# 8k-nolink.net
KiCad netlist of a schematic drawn in EAGLE
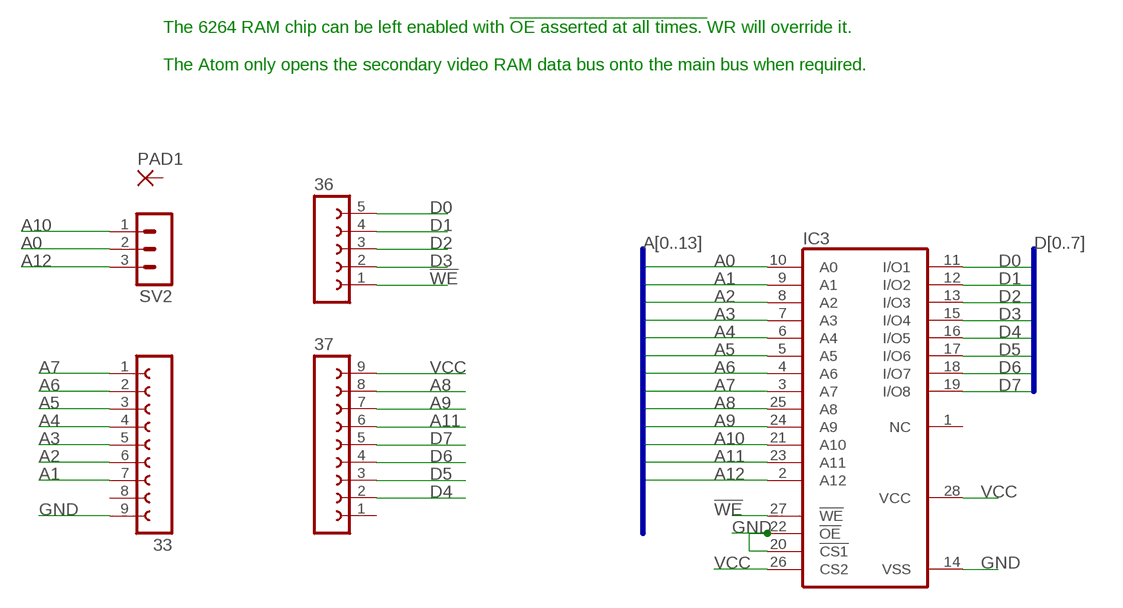
[diagram p0: schematic, sheet 1]

(export (version "E")
  (design (tool "Eeschema 10.0.6"))
  (components
    (comp (ref "33")
      (value "FE09-1")
      (footprint "eagle-import:FE09")
      (libsource (lib "eagle-import") (part "FE09-1"))
    )
    (comp (ref "36")
      (value "FE05-1")
      (footprint "eagle-import:FE05-1")
      (libsource (lib "eagle-import") (part "FE05-1"))
    )
    (comp (ref "37")
      (value "FE09-1")
      (footprint "eagle-import:FE09")
      (libsource (lib "eagle-import") (part "FE09-1"))
    )
    (comp (ref "IC3")
      (value "6264A")
      (footprint "eagle-import:DIL28-6")
      (libsource (lib "eagle-import") (part "6264A"))
    )
    (comp (ref "PAD1")
      (value "1,6/0,8")
      (footprint "eagle-import:1,6_0,8")
      (libsource (lib "eagle-import") (part "1,6/0,8"))
    )
    (comp (ref "SV2")
      (value "MA03-1")
      (footprint "eagle-import:MA03-1")
      (libsource (lib "eagle-import") (part "MA03-1"))
    )
  )
  (nets
    (net (code "2") (name "/A0") (class "Default")
      (node (ref "IC3") (pin "10") (pinfunction "A0_10") (pintype "input"))
      (node (ref "SV2") (pin "2") (pinfunction "2_2") (pintype "passive"))
    )
    (net (code "3") (name "/A1") (class "Default")
      (node (ref "33") (pin "7") (pinfunction "7_7") (pintype "passive"))
      (node (ref "IC3") (pin "9") (pinfunction "A1_9") (pintype "input"))
    )
    (net (code "4") (name "/A2") (class "Default")
      (node (ref "33") (pin "6") (pinfunction "6_6") (pintype "passive"))
      (node (ref "IC3") (pin "8") (pinfunction "A2_8") (pintype "input"))
    )
    (net (code "5") (name "/A3") (class "Default")
      (node (ref "33") (pin "5") (pinfunction "5_5") (pintype "passive"))
      (node (ref "IC3") (pin "7") (pinfunction "A3_7") (pintype "input"))
    )
    (net (code "6") (name "/A4") (class "Default")
      (node (ref "33") (pin "4") (pinfunction "4_4") (pintype "passive"))
      (node (ref "IC3") (pin "6") (pinfunction "A4_6") (pintype "input"))
    )
    (net (code "7") (name "/A5") (class "Default")
      (node (ref "33") (pin "3") (pinfunction "3_3") (pintype "passive"))
      (node (ref "IC3") (pin "5") (pinfunction "A5_5") (pintype "input"))
    )
    (net (code "8") (name "/A6") (class "Default")
      (node (ref "33") (pin "2") (pinfunction "2_2") (pintype "passive"))
      (node (ref "IC3") (pin "4") (pinfunction "A6_4") (pintype "input"))
    )
    (net (code "9") (name "/A7") (class "Default")
      (node (ref "33") (pin "1") (pinfunction "1_1") (pintype "passive"))
      (node (ref "IC3") (pin "3") (pinfunction "A7_3") (pintype "input"))
    )
    (net (code "10") (name "/A8") (class "Default")
      (node (ref "37") (pin "8") (pinfunction "8_8") (pintype "passive"))
      (node (ref "IC3") (pin "25") (pinfunction "A8_25") (pintype "input"))
    )
    (net (code "11") (name "/A9") (class "Default")
      (node (ref "37") (pin "7") (pinfunction "7_7") (pintype "passive"))
      (node (ref "IC3") (pin "24") (pinfunction "A9_24") (pintype "input"))
    )
    (net (code "12") (name "/A10") (class "Default")
      (node (ref "IC3") (pin "21") (pinfunction "A10_21") (pintype "input"))
      (node (ref "SV2") (pin "1") (pinfunction "1_1") (pintype "passive"))
    )
    (net (code "13") (name "/A11") (class "Default")
      (node (ref "37") (pin "6") (pinfunction "6_6") (pintype "passive"))
      (node (ref "IC3") (pin "23") (pinfunction "A11_23") (pintype "input"))
    )
    (net (code "14") (name "/A12") (class "Default")
      (node (ref "IC3") (pin "2") (pinfunction "A12_2") (pintype "input"))
      (node (ref "SV2") (pin "3") (pinfunction "3_3") (pintype "passive"))
    )
    (net (code "16") (name "/D0") (class "Default")
      (node (ref "36") (pin "5") (pinfunction "5_5") (pintype "passive"))
      (node (ref "IC3") (pin "11") (pinfunction "I/O1_11") (pintype "bidirectional"))
    )
    (net (code "17") (name "/D1") (class "Default")
      (node (ref "36") (pin "4") (pinfunction "4_4") (pintype "passive"))
      (node (ref "IC3") (pin "12") (pinfunction "I/O2_12") (pintype "bidirectional"))
    )
    (net (code "18") (name "/D2") (class "Default")
      (node (ref "36") (pin "3") (pinfunction "3_3") (pintype "passive"))
      (node (ref "IC3") (pin "13") (pinfunction "I/O3_13") (pintype "bidirectional"))
    )
    (net (code "19") (name "/D3") (class "Default")
      (node (ref "36") (pin "2") (pinfunction "2_2") (pintype "passive"))
      (node (ref "IC3") (pin "15") (pinfunction "I/O4_15") (pintype "bidirectional"))
    )
    (net (code "20") (name "/D4") (class "Default")
      (node (ref "37") (pin "2") (pinfunction "2_2") (pintype "passive"))
      (node (ref "IC3") (pin "16") (pinfunction "I/O5_16") (pintype "bidirectional"))
    )
    (net (code "21") (name "/D5") (class "Default")
      (node (ref "37") (pin "3") (pinfunction "3_3") (pintype "passive"))
      (node (ref "IC3") (pin "17") (pinfunction "I/O6_17") (pintype "bidirectional"))
    )
    (net (code "22") (name "/D6") (class "Default")
      (node (ref "37") (pin "4") (pinfunction "4_4") (pintype "passive"))
      (node (ref "IC3") (pin "18") (pinfunction "I/O7_18") (pintype "bidirectional"))
    )
    (net (code "23") (name "/D7") (class "Default")
      (node (ref "37") (pin "5") (pinfunction "5_5") (pintype "passive"))
      (node (ref "IC3") (pin "19") (pinfunction "I/O8_19") (pintype "bidirectional"))
    )
    (net (code "25") (name "/GND") (class "Default")
      (node (ref "33") (pin "9") (pinfunction "9_9") (pintype "passive"))
      (node (ref "IC3") (pin "14") (pinfunction "VSS_14") (pintype "power_in"))
      (node (ref "IC3") (pin "20") (pinfunction "~{CS1}_20") (pintype "input"))
      (node (ref "IC3") (pin "22") (pinfunction "~{OE}_22") (pintype "input"))
    )
    (net (code "26") (name "/VCC") (class "Default")
      (node (ref "37") (pin "9") (pinfunction "9_9") (pintype "passive"))
      (node (ref "IC3") (pin "26") (pinfunction "CS2_26") (pintype "input"))
      (node (ref "IC3") (pin "28") (pinfunction "VCC_28") (pintype "power_in"))
    )
    (net (code "27") (name "/~{WE}") (class "Default")
      (node (ref "36") (pin "1") (pinfunction "1_1") (pintype "passive"))
      (node (ref "IC3") (pin "27") (pinfunction "~{WE}_27") (pintype "input"))
    )
    (net (code "28") (name "unconnected-(33-Pad8)") (class "Default")
      (node (ref "33") (pin "8") (pinfunction "8_8") (pintype "passive"))
    )
    (net (code "29") (name "unconnected-(37-Pad1)") (class "Default")
      (node (ref "37") (pin "1") (pinfunction "1_1") (pintype "passive"))
    )
    (net (code "30") (name "unconnected-(IC3-NC-Pad1)") (class "Default")
      (node (ref "IC3") (pin "1") (pinfunction "NC_1") (pintype "no_connect"))
    )
    (net (code "31") (name "unconnected-(PAD1-P-Pad1)") (class "Default")
      (node (ref "PAD1") (pin "1") (pinfunction "P_1") (pintype "passive"))
    )
  )
)
